# Sheet1.net
KiCad netlist of a schematic drawn in Altium Designer
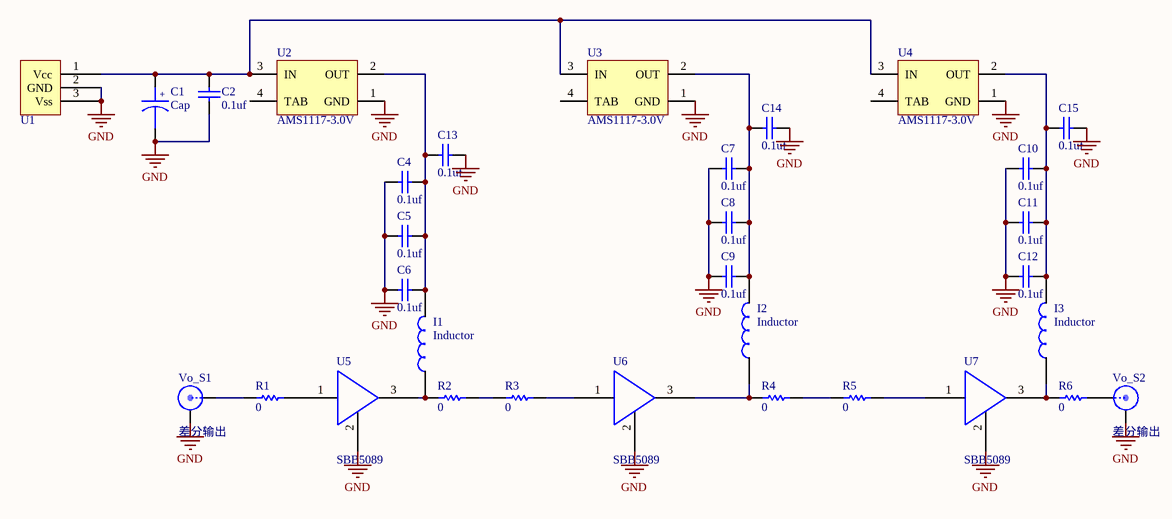
[diagram p0: Sheet1.SchDoc]

(export (version "E")
  (design (tool "Eeschema 10.0.6"))
  (components
    (comp (ref "C1")
      (value "Cap")
      (footprint "3216C-TYPE_A")
      (libsource (lib "Schlib1") (part "Tantalium Cap"))
    )
    (comp (ref "C2") (value "0.1uf") (footprint "3216C-TYPE_A") (libsource (lib "Schlib1") (part "Cap")))
    (comp (ref "C4") (value "0.1uf") (footprint "0603C") (libsource (lib "Schlib1") (part "Cap")))
    (comp (ref "C5") (value "0.1uf") (footprint "0603C") (libsource (lib "Schlib1") (part "Cap")))
    (comp (ref "C6") (value "0.1uf") (footprint "0603C") (libsource (lib "Schlib1") (part "Cap")))
    (comp (ref "C7") (value "0.1uf") (footprint "0603C") (libsource (lib "Schlib1") (part "Cap")))
    (comp (ref "C8") (value "0.1uf") (footprint "0603C") (libsource (lib "Schlib1") (part "Cap")))
    (comp (ref "C9") (value "0.1uf") (footprint "0603C") (libsource (lib "Schlib1") (part "Cap")))
    (comp (ref "C10") (value "0.1uf") (footprint "0603C") (libsource (lib "Schlib1") (part "Cap")))
    (comp (ref "C11") (value "0.1uf") (footprint "0603C") (libsource (lib "Schlib1") (part "Cap")))
    (comp (ref "C12") (value "0.1uf") (footprint "0603C") (libsource (lib "Schlib1") (part "Cap")))
    (comp (ref "C13") (value "0.1uf") (footprint "3216C-TYPE_A") (libsource (lib "Schlib1") (part "Cap")))
    (comp (ref "C14") (value "0.1uf") (footprint "3216C-TYPE_A") (libsource (lib "Schlib1") (part "Cap")))
    (comp (ref "C15") (value "0.1uf") (footprint "3216C-TYPE_A") (libsource (lib "Schlib1") (part "Cap")))
    (comp (ref "I1") (value "Inductor") (footprint "0603R") (libsource (lib "Schlib1") (part "Inductor")))
    (comp (ref "I2") (value "Inductor") (footprint "0603R") (libsource (lib "Schlib1") (part "Inductor")))
    (comp (ref "I3") (value "Inductor") (footprint "0603R") (libsource (lib "Schlib1") (part "Inductor")))
    (comp (ref "R1") (value "0") (footprint "0603R") (libsource (lib "Schlib1") (part "Res")))
    (comp (ref "R2") (value "0") (footprint "0603R") (libsource (lib "Schlib1") (part "Res")))
    (comp (ref "R3") (value "0") (footprint "0603R") (libsource (lib "Schlib1") (part "Res")))
    (comp (ref "R4") (value "0") (footprint "0603R") (libsource (lib "Schlib1") (part "Res")))
    (comp (ref "R5") (value "0") (footprint "0603R") (libsource (lib "Schlib1") (part "Res")))
    (comp (ref "R6") (value "0") (footprint "0603R") (libsource (lib "Schlib1") (part "Res")))
    (comp (ref "U1")
      (value "XH2.54-3p")
      (footprint "XH2.54-3p")
      (libsource (lib "Schlib1") (part "XH2.54-3p"))
    )
    (comp (ref "U2")
      (value "AMS1117-3.0V")
      (footprint "SOT-223")
      (libsource (lib "Schlib1") (part "AMS1117-3.0V"))
    )
    (comp (ref "U3")
      (value "AMS1117-3.0V")
      (footprint "SOT-223")
      (libsource (lib "Schlib1") (part "AMS1117-3.0V"))
    )
    (comp (ref "U4")
      (value "AMS1117-3.0V")
      (footprint "SOT-223")
      (libsource (lib "Schlib1") (part "AMS1117-3.0V"))
    )
    (comp (ref "U5") (value "SBB5089") (footprint "SOT-89") (libsource (lib "Schlib1") (part "SBB5089")))
    (comp (ref "U6") (value "SBB5089") (footprint "SOT-89") (libsource (lib "Schlib1") (part "SBB5089")))
    (comp (ref "U7") (value "SBB5089") (footprint "SOT-89") (libsource (lib "Schlib1") (part "SBB5089")))
    (comp (ref "Vo_S1") (value "差分输出") (footprint "SMA Angle") (libsource (lib "Schlib1") (part "SMA")))
    (comp (ref "Vo_S2") (value "差分输出") (footprint "SMA Angle") (libsource (lib "Schlib1") (part "SMA")))
  )
  (nets
    (net (code "1") (name "GND") (class "Default")
      (node (ref "C1") (pin "2") (pinfunction "2_2") (pintype "passive"))
      (node (ref "C10") (pin "1") (pinfunction "1_1") (pintype "passive"))
      (node (ref "C11") (pin "1") (pinfunction "1_1") (pintype "passive"))
      (node (ref "C12") (pin "1") (pinfunction "1_1") (pintype "passive"))
      (node (ref "C13") (pin "2") (pinfunction "2_2") (pintype "passive"))
      (node (ref "C14") (pin "2") (pinfunction "2_2") (pintype "passive"))
      (node (ref "C15") (pin "2") (pinfunction "2_2") (pintype "passive"))
      (node (ref "C2") (pin "1") (pinfunction "1_1") (pintype "passive"))
      (node (ref "C4") (pin "1") (pinfunction "1_1") (pintype "passive"))
      (node (ref "C5") (pin "1") (pinfunction "1_1") (pintype "passive"))
      (node (ref "C6") (pin "1") (pinfunction "1_1") (pintype "passive"))
      (node (ref "C7") (pin "1") (pinfunction "1_1") (pintype "passive"))
      (node (ref "C8") (pin "1") (pinfunction "1_1") (pintype "passive"))
      (node (ref "C9") (pin "1") (pinfunction "1_1") (pintype "passive"))
      (node (ref "U1") (pin "2") (pinfunction "GND_2") (pintype "passive"))
      (node (ref "U1") (pin "3") (pinfunction "Vss_3") (pintype "passive"))
      (node (ref "U2") (pin "1") (pinfunction "GND_1") (pintype "power_in"))
      (node (ref "U3") (pin "1") (pinfunction "GND_1") (pintype "power_in"))
      (node (ref "U4") (pin "1") (pinfunction "GND_1") (pintype "power_in"))
      (node (ref "U5") (pin "2") (pinfunction "GND_2") (pintype "passive"))
      (node (ref "U6") (pin "2") (pinfunction "GND_2") (pintype "passive"))
      (node (ref "U7") (pin "2") (pinfunction "GND_2") (pintype "passive"))
      (node (ref "Vo_S1") (pin "1") (pinfunction "1_1") (pintype "passive"))
      (node (ref "Vo_S2") (pin "1") (pinfunction "1_1") (pintype "passive"))
    )
    (net (code "2") (name "Net-(R1-Pad1)") (class "Default")
      (node (ref "R1") (pin "1") (pinfunction "1_1") (pintype "passive"))
      (node (ref "Vo_S1") (pin "0") (pinfunction "0_0") (pintype "passive"))
    )
    (net (code "3") (name "Net-(R2-Pad2)") (class "Default")
      (node (ref "R2") (pin "2") (pinfunction "2_2") (pintype "passive"))
      (node (ref "R3") (pin "1") (pinfunction "1_1") (pintype "passive"))
    )
    (net (code "4") (name "Net-(R4-Pad2)") (class "Default")
      (node (ref "R4") (pin "2") (pinfunction "2_2") (pintype "passive"))
      (node (ref "R5") (pin "1") (pinfunction "1_1") (pintype "passive"))
    )
    (net (code "5") (name "Net-(R6-Pad2)") (class "Default")
      (node (ref "R6") (pin "2") (pinfunction "2_2") (pintype "passive"))
      (node (ref "Vo_S2") (pin "0") (pinfunction "0_0") (pintype "passive"))
    )
    (net (code "6") (name "Net-(U1-Vcc)") (class "Default")
      (node (ref "C1") (pin "1") (pinfunction "1_1") (pintype "passive"))
      (node (ref "C2") (pin "2") (pinfunction "2_2") (pintype "passive"))
      (node (ref "U1") (pin "1") (pinfunction "Vcc_1") (pintype "passive"))
      (node (ref "U2") (pin "3") (pinfunction "IN_3") (pintype "power_in"))
      (node (ref "U3") (pin "3") (pinfunction "IN_3") (pintype "power_in"))
      (node (ref "U4") (pin "3") (pinfunction "IN_3") (pintype "power_in"))
    )
    (net (code "7") (name "Net-(U2-OUT)") (class "Default")
      (node (ref "C13") (pin "1") (pinfunction "1_1") (pintype "passive"))
      (node (ref "C4") (pin "2") (pinfunction "2_2") (pintype "passive"))
      (node (ref "C5") (pin "2") (pinfunction "2_2") (pintype "passive"))
      (node (ref "C6") (pin "2") (pinfunction "2_2") (pintype "passive"))
      (node (ref "I1") (pin "2") (pintype "passive"))
      (node (ref "U2") (pin "2") (pinfunction "OUT_2") (pintype "power_in"))
    )
    (net (code "8") (name "Net-(U3-OUT)") (class "Default")
      (node (ref "C14") (pin "1") (pinfunction "1_1") (pintype "passive"))
      (node (ref "C7") (pin "2") (pinfunction "2_2") (pintype "passive"))
      (node (ref "C8") (pin "2") (pinfunction "2_2") (pintype "passive"))
      (node (ref "C9") (pin "2") (pinfunction "2_2") (pintype "passive"))
      (node (ref "I2") (pin "2") (pintype "passive"))
      (node (ref "U3") (pin "2") (pinfunction "OUT_2") (pintype "power_in"))
    )
    (net (code "9") (name "Net-(U4-OUT)") (class "Default")
      (node (ref "C10") (pin "2") (pinfunction "2_2") (pintype "passive"))
      (node (ref "C11") (pin "2") (pinfunction "2_2") (pintype "passive"))
      (node (ref "C12") (pin "2") (pinfunction "2_2") (pintype "passive"))
      (node (ref "C15") (pin "1") (pinfunction "1_1") (pintype "passive"))
      (node (ref "I3") (pin "2") (pintype "passive"))
      (node (ref "U4") (pin "2") (pinfunction "OUT_2") (pintype "power_in"))
    )
    (net (code "10") (name "Net-(U5-IN)") (class "Default")
      (node (ref "R1") (pin "2") (pinfunction "2_2") (pintype "passive"))
      (node (ref "U5") (pin "1") (pinfunction "IN_1") (pintype "passive"))
    )
    (net (code "11") (name "Net-(U5-OUT)") (class "Default")
      (node (ref "I1") (pin "1") (pintype "passive"))
      (node (ref "R2") (pin "1") (pinfunction "1_1") (pintype "passive"))
      (node (ref "U5") (pin "3") (pinfunction "OUT_3") (pintype "passive"))
    )
    (net (code "12") (name "Net-(U6-IN)") (class "Default")
      (node (ref "R3") (pin "2") (pinfunction "2_2") (pintype "passive"))
      (node (ref "U6") (pin "1") (pinfunction "IN_1") (pintype "passive"))
    )
    (net (code "13") (name "Net-(U6-OUT)") (class "Default")
      (node (ref "I2") (pin "1") (pintype "passive"))
      (node (ref "R4") (pin "1") (pinfunction "1_1") (pintype "passive"))
      (node (ref "U6") (pin "3") (pinfunction "OUT_3") (pintype "passive"))
    )
    (net (code "14") (name "Net-(U7-IN)") (class "Default")
      (node (ref "R5") (pin "2") (pinfunction "2_2") (pintype "passive"))
      (node (ref "U7") (pin "1") (pinfunction "IN_1") (pintype "passive"))
    )
    (net (code "15") (name "Net-(U7-OUT)") (class "Default")
      (node (ref "I3") (pin "1") (pintype "passive"))
      (node (ref "R6") (pin "1") (pinfunction "1_1") (pintype "passive"))
      (node (ref "U7") (pin "3") (pinfunction "OUT_3") (pintype "passive"))
    )
    (net (code "16") (name "unconnected-(U2-TAB-Pad4)") (class "Default")
      (node (ref "U2") (pin "4") (pinfunction "TAB_4") (pintype "power_in"))
    )
    (net (code "17") (name "unconnected-(U3-TAB-Pad4)") (class "Default")
      (node (ref "U3") (pin "4") (pinfunction "TAB_4") (pintype "power_in"))
    )
    (net (code "18") (name "unconnected-(U4-TAB-Pad4)") (class "Default")
      (node (ref "U4") (pin "4") (pinfunction "TAB_4") (pintype "power_in"))
    )
  )
)
